# NetCamera.net
KiCad netlist of a schematic drawn in Altium Designer
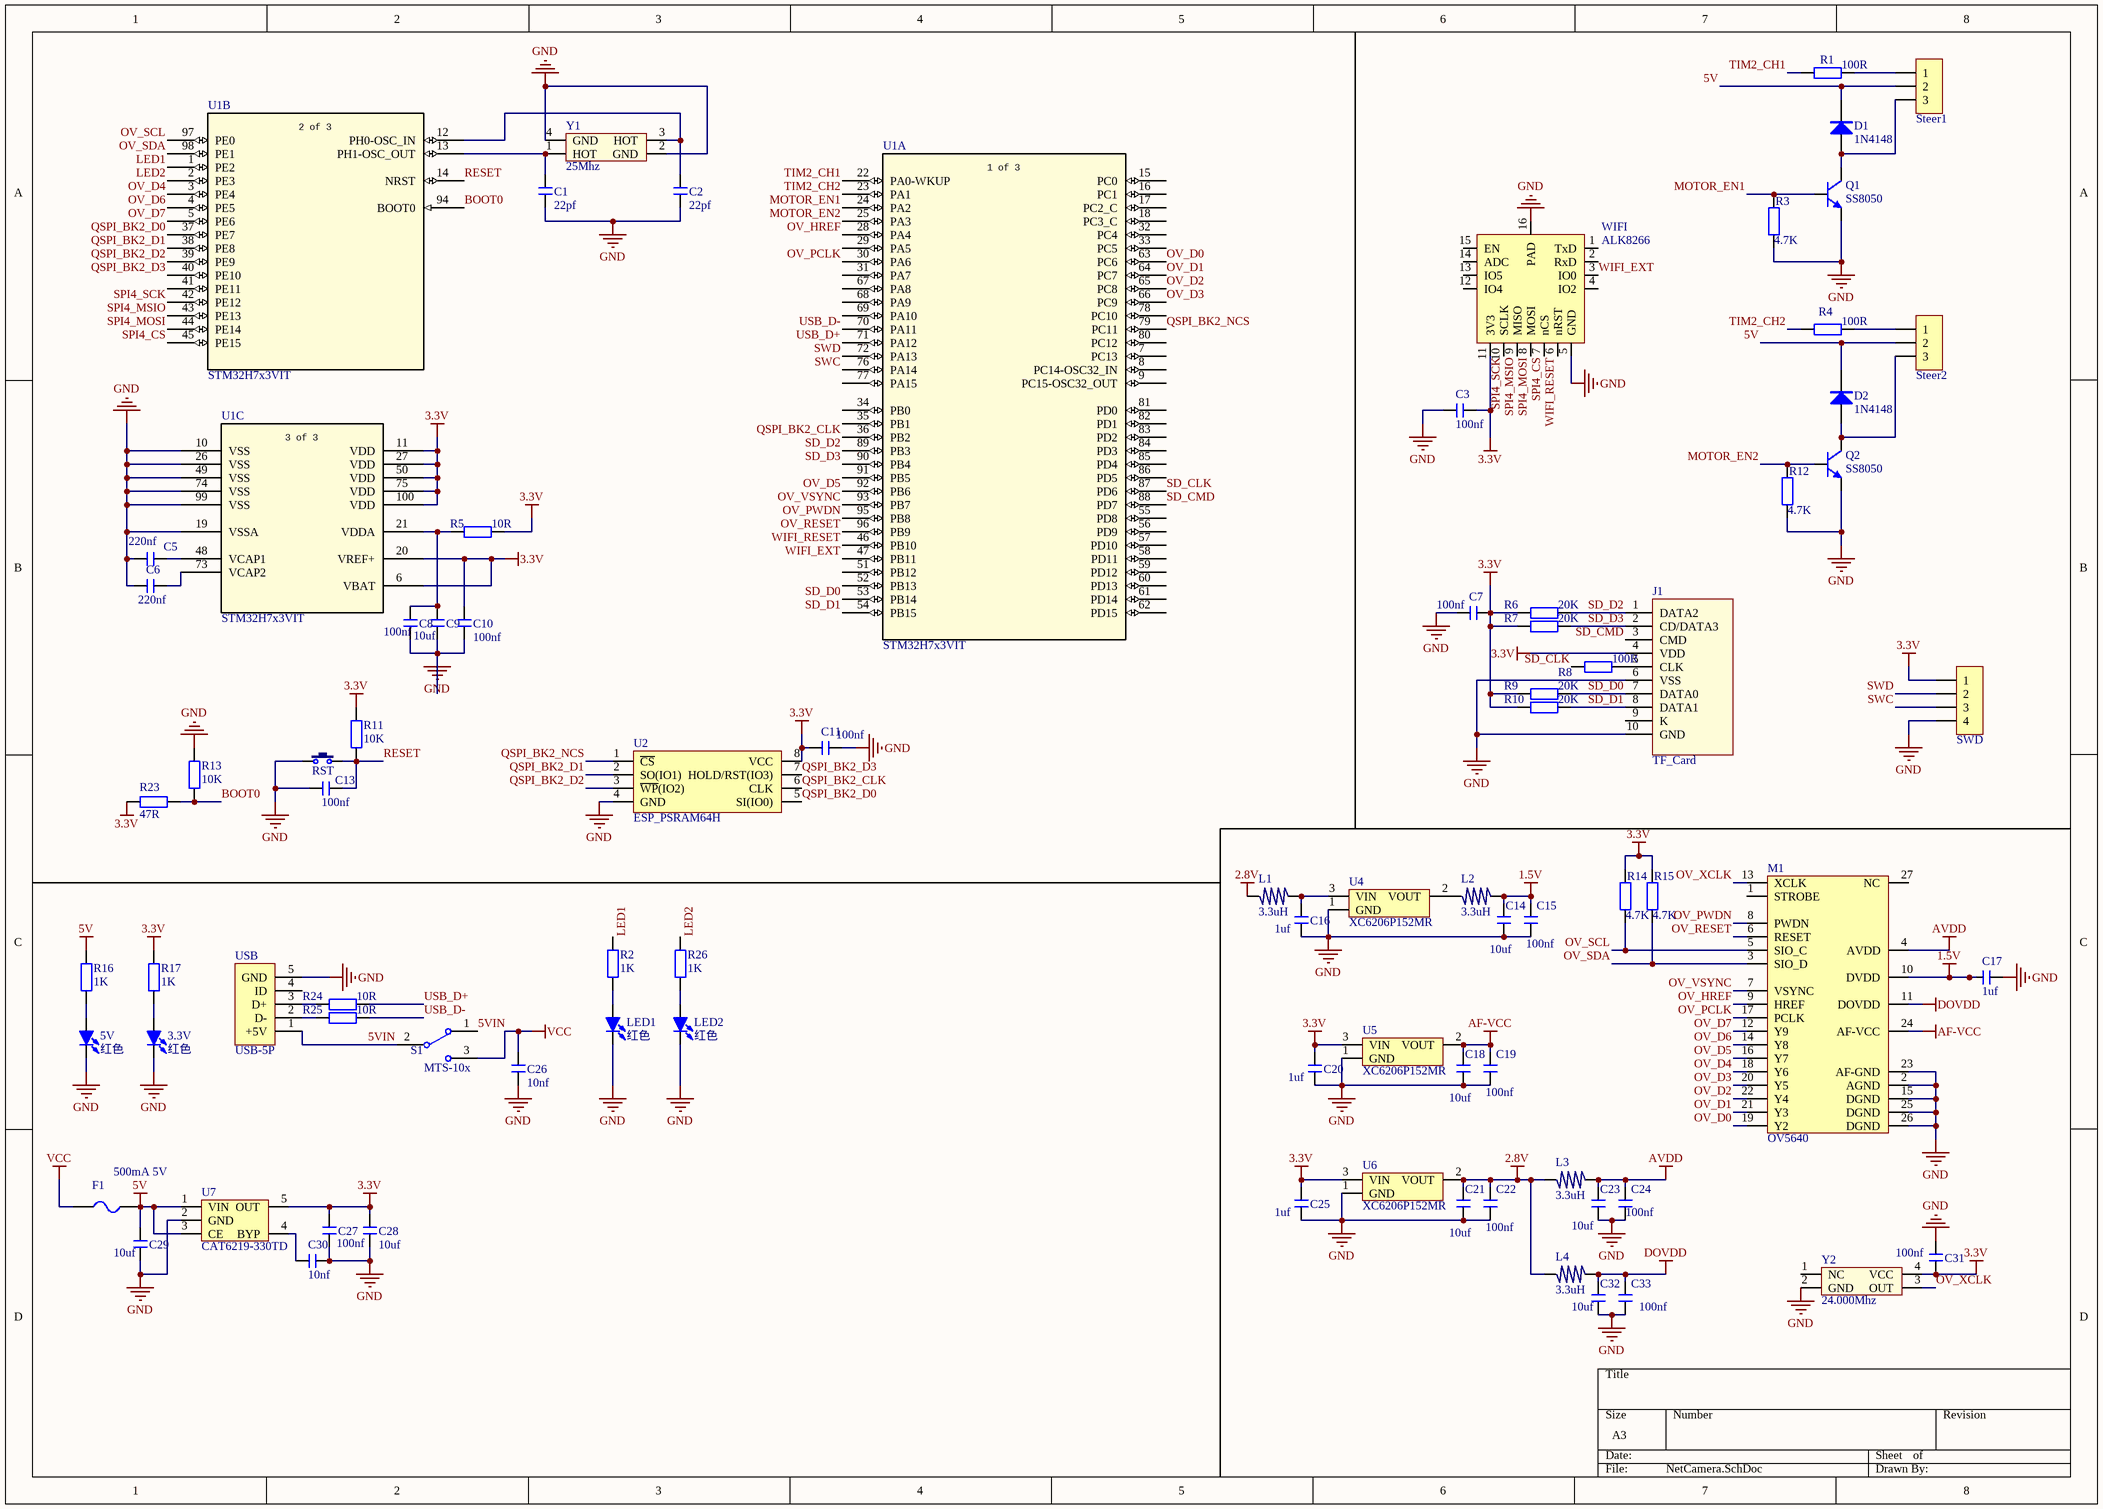
[diagram p0: NetCamera.SchDoc]

(export (version "E")
  (design (tool "Eeschema 10.0.6"))
  (components
    (comp (ref "3.3V")
      (value "红色")
      (footprint "LED 0603R")
      (description "贴片LED")
      (fields (field (name "版权归属") "源创客"))
      (libsource (lib "9.1   - LED") (part "LED-SMD"))
    )
    (comp (ref "5V")
      (value "红色")
      (footprint "LED 0603R")
      (description "贴片LED")
      (fields (field (name "版权归属") "源创客"))
      (libsource (lib "9.1   - LED") (part "LED-SMD"))
    )
    (comp (ref "C1")
      (value "22pf")
      (footprint "C 0603_L")
      (description "无极性贴片电容")
      (fields (field (name "版权归属") "源创客"))
      (libsource (lib "3.1   - 电阻-电容-电感") (part "C"))
    )
    (comp (ref "C2")
      (value "22pf")
      (footprint "C 0603_L")
      (description "无极性贴片电容")
      (fields (field (name "版权归属") "源创客"))
      (libsource (lib "3.1   - 电阻-电容-电感") (part "C"))
    )
    (comp (ref "C3")
      (value "100nf")
      (footprint "C 0603_L")
      (description "无极性贴片电容")
      (fields (field (name "版权归属") "源创客"))
      (libsource (lib "3.1   - 电阻-电容-电感") (part "C"))
    )
    (comp (ref "C5")
      (value "220nf")
      (footprint "C 0603_L")
      (description "无极性贴片电容")
      (fields (field (name "版权归属") "源创客"))
      (libsource (lib "3.1   - 电阻-电容-电感") (part "C"))
    )
    (comp (ref "C6")
      (value "220nf")
      (footprint "C 0603_L")
      (description "无极性贴片电容")
      (fields (field (name "版权归属") "源创客"))
      (libsource (lib "3.1   - 电阻-电容-电感") (part "C"))
    )
    (comp (ref "C7")
      (value "100nf")
      (footprint "C 0603_L")
      (description "无极性贴片电容")
      (fields (field (name "版权归属") "源创客"))
      (libsource (lib "3.1   - 电阻-电容-电感") (part "C"))
    )
    (comp (ref "C8")
      (value "100nf")
      (footprint "C 0603_L")
      (description "无极性贴片电容")
      (fields (field (name "版权归属") "源创客"))
      (libsource (lib "3.1   - 电阻-电容-电感") (part "C"))
    )
    (comp (ref "C9")
      (value "10uf")
      (footprint "C 0603_L")
      (description "无极性贴片电容")
      (fields (field (name "版权归属") "源创客"))
      (libsource (lib "3.1   - 电阻-电容-电感") (part "C"))
    )
    (comp (ref "C10")
      (value "100nf")
      (footprint "C 0603_L")
      (description "无极性贴片电容")
      (fields (field (name "版权归属") "源创客"))
      (libsource (lib "3.1   - 电阻-电容-电感") (part "C"))
    )
    (comp (ref "C11")
      (value "100nf")
      (footprint "C 0603_L")
      (description "无极性贴片电容")
      (fields (field (name "版权归属") "源创客"))
      (libsource (lib "3.1   - 电阻-电容-电感") (part "C"))
    )
    (comp (ref "C13")
      (value "100nf")
      (footprint "C 0603_L")
      (description "无极性贴片电容")
      (fields (field (name "版权归属") "源创客"))
      (libsource (lib "3.1   - 电阻-电容-电感") (part "C"))
    )
    (comp (ref "C14")
      (value "10uf")
      (footprint "C 0805_L")
      (description "无极性贴片电容")
      (fields (field (name "版权归属") "源创客"))
      (libsource (lib "3.1   - 电阻-电容-电感") (part "C"))
    )
    (comp (ref "C15")
      (value "100nf")
      (footprint "C 0603_L")
      (description "无极性贴片电容")
      (fields (field (name "版权归属") "源创客"))
      (libsource (lib "3.1   - 电阻-电容-电感") (part "C"))
    )
    (comp (ref "C16")
      (value "1uf")
      (footprint "C 0603_L")
      (description "无极性贴片电容")
      (fields (field (name "版权归属") "源创客"))
      (libsource (lib "3.1   - 电阻-电容-电感") (part "C"))
    )
    (comp (ref "C17")
      (value "1uf")
      (footprint "C 0805_L")
      (description "无极性贴片电容")
      (fields (field (name "版权归属") "源创客"))
      (libsource (lib "3.1   - 电阻-电容-电感") (part "C"))
    )
    (comp (ref "C18")
      (value "10uf")
      (footprint "C 0805_L")
      (description "无极性贴片电容")
      (fields (field (name "版权归属") "源创客"))
      (libsource (lib "3.1   - 电阻-电容-电感") (part "C"))
    )
    (comp (ref "C19")
      (value "100nf")
      (footprint "C 0603_L")
      (description "无极性贴片电容")
      (fields (field (name "版权归属") "源创客"))
      (libsource (lib "3.1   - 电阻-电容-电感") (part "C"))
    )
    (comp (ref "C20")
      (value "1uf")
      (footprint "C 0603_L")
      (description "无极性贴片电容")
      (fields (field (name "版权归属") "源创客"))
      (libsource (lib "3.1   - 电阻-电容-电感") (part "C"))
    )
    (comp (ref "C21")
      (value "10uf")
      (footprint "C 0805_L")
      (description "无极性贴片电容")
      (fields (field (name "版权归属") "源创客"))
      (libsource (lib "3.1   - 电阻-电容-电感") (part "C"))
    )
    (comp (ref "C22")
      (value "100nf")
      (footprint "C 0603_L")
      (description "无极性贴片电容")
      (fields (field (name "版权归属") "源创客"))
      (libsource (lib "3.1   - 电阻-电容-电感") (part "C"))
    )
    (comp (ref "C23")
      (value "10uf")
      (footprint "C 0805_L")
      (description "无极性贴片电容")
      (fields (field (name "版权归属") "源创客"))
      (libsource (lib "3.1   - 电阻-电容-电感") (part "C"))
    )
    (comp (ref "C24")
      (value "100nf")
      (footprint "C 0603_L")
      (description "无极性贴片电容")
      (fields (field (name "版权归属") "源创客"))
      (libsource (lib "3.1   - 电阻-电容-电感") (part "C"))
    )
    (comp (ref "C25")
      (value "1uf")
      (footprint "C 0603_L")
      (description "无极性贴片电容")
      (fields (field (name "版权归属") "源创客"))
      (libsource (lib "3.1   - 电阻-电容-电感") (part "C"))
    )
    (comp (ref "C26")
      (value "10nf")
      (footprint "C 0805_L")
      (description "无极性贴片电容")
      (fields (field (name "版权归属") "源创客"))
      (libsource (lib "3.1   - 电阻-电容-电感") (part "C"))
    )
    (comp (ref "C27")
      (value "100nf")
      (footprint "C 0603_L")
      (description "无极性贴片电容")
      (fields (field (name "版权归属") "源创客"))
      (libsource (lib "3.1   - 电阻-电容-电感") (part "C"))
    )
    (comp (ref "C28")
      (value "10uf")
      (footprint "C 0805_L")
      (description "无极性贴片电容")
      (fields (field (name "版权归属") "源创客"))
      (libsource (lib "3.1   - 电阻-电容-电感") (part "C"))
    )
    (comp (ref "C29")
      (value "10uf")
      (footprint "C 0603_L")
      (description "无极性贴片电容")
      (fields (field (name "版权归属") "源创客"))
      (libsource (lib "3.1   - 电阻-电容-电感") (part "C"))
    )
    (comp (ref "C30")
      (value "10nf")
      (footprint "C 0603_L")
      (description "无极性贴片电容")
      (fields (field (name "版权归属") "源创客"))
      (libsource (lib "3.1   - 电阻-电容-电感") (part "C"))
    )
    (comp (ref "C31")
      (value "100nf")
      (footprint "C 0603_L")
      (description "无极性贴片电容")
      (fields (field (name "版权归属") "源创客"))
      (libsource (lib "3.1   - 电阻-电容-电感") (part "C"))
    )
    (comp (ref "C32")
      (value "10uf")
      (footprint "C 0805_L")
      (description "无极性贴片电容")
      (fields (field (name "版权归属") "源创客"))
      (libsource (lib "3.1   - 电阻-电容-电感") (part "C"))
    )
    (comp (ref "C33")
      (value "100nf")
      (footprint "C 0603_L")
      (description "无极性贴片电容")
      (fields (field (name "版权归属") "源创客"))
      (libsource (lib "3.1   - 电阻-电容-电感") (part "C"))
    )
    (comp (ref "D1")
      (value "1N4148")
      (footprint "SOD-323")
      (description "高速开关二极管")
      (fields (field (name "版权归属") "源创客"))
      (libsource (lib "8.1   - 二极管-整流桥") (part "1N4148"))
    )
    (comp (ref "D2")
      (value "1N4148")
      (footprint "SOD-323")
      (description "高速开关二极管")
      (fields (field (name "版权归属") "源创客"))
      (libsource (lib "8.1   - 二极管-整流桥") (part "1N4148"))
    )
    (comp (ref "F1")
      (value "500mA 5V")
      (footprint "FU 0805")
      (description "贴片保险丝")
      (fields (field (name "版权归属") "源创客"))
      (libsource (lib "10.1 - 保险丝-晶振") (part "FU"))
    )
    (comp (ref "J1")
      (value "TF_Card")
      (footprint "Micro SD")
      (description "TF卡座")
      (fields (field (name "版权归属") "源创客"))
      (libsource (lib "4.1   - 接口类") (part "TF_Card"))
    )
    (comp (ref "L1") (value "3.3uH") (footprint "L 0805") (libsource (lib "ATK-OV5640摄像头模块封装库") (part "L")))
    (comp (ref "L2") (value "3.3uH") (footprint "L 0805") (libsource (lib "ATK-OV5640摄像头模块封装库") (part "L")))
    (comp (ref "L3") (value "3.3uH") (footprint "L 0805") (libsource (lib "ATK-OV5640摄像头模块封装库") (part "L")))
    (comp (ref "L4") (value "3.3uH") (footprint "L 0805") (libsource (lib "ATK-OV5640摄像头模块封装库") (part "L")))
    (comp (ref "LED1")
      (value "红色")
      (footprint "LED 0603R")
      (description "贴片LED")
      (fields (field (name "版权归属") "源创客"))
      (libsource (lib "9.1   - LED") (part "LED-SMD"))
    )
    (comp (ref "LED2")
      (value "红色")
      (footprint "LED 0603R")
      (description "贴片LED")
      (fields (field (name "版权归属") "源创客"))
      (libsource (lib "9.1   - LED") (part "LED-SMD"))
    )
    (comp (ref "M1")
      (value "OV5640")
      (footprint "OV5640-24")
      (description "OV5640模组,AF,FPC")
      (libsource (lib "ATK-OV5640摄像头模块封装库") (part "OV5640"))
    )
    (comp (ref "Q1")
      (value "SS8050")
      (footprint "SOT23-3N")
      (description "高频放大-NPN型")
      (fields (field (name "版权归属") "源创客"))
      (libsource (lib "6.2   - 三极管") (part "8050-SMD"))
    )
    (comp (ref "Q2")
      (value "SS8050")
      (footprint "SOT23-3N")
      (description "高频放大-NPN型")
      (fields (field (name "版权归属") "源创客"))
      (libsource (lib "6.2   - 三极管") (part "8050-SMD"))
    )
    (comp (ref "R1")
      (value "100R")
      (footprint "R 0603_L")
      (description "贴片电阻")
      (fields (field (name "版权归属") "源创客"))
      (libsource (lib "3.1   - 电阻-电容-电感") (part "R"))
    )
    (comp (ref "R2")
      (value "1K")
      (footprint "R 0603_L")
      (description "贴片电阻")
      (fields (field (name "版权归属") "源创客"))
      (libsource (lib "3.1   - 电阻-电容-电感") (part "R"))
    )
    (comp (ref "R3")
      (value "4.7K")
      (footprint "R 0603_L")
      (description "贴片电阻")
      (fields (field (name "版权归属") "源创客"))
      (libsource (lib "3.1   - 电阻-电容-电感") (part "R"))
    )
    (comp (ref "R4")
      (value "100R")
      (footprint "R 0603_L")
      (description "贴片电阻")
      (fields (field (name "版权归属") "源创客"))
      (libsource (lib "3.1   - 电阻-电容-电感") (part "R"))
    )
    (comp (ref "R5")
      (value "10R")
      (footprint "R 0603_L")
      (description "贴片电阻")
      (fields (field (name "版权归属") "源创客"))
      (libsource (lib "3.1   - 电阻-电容-电感") (part "R"))
    )
    (comp (ref "R6")
      (value "20K")
      (footprint "R 0603_L")
      (description "贴片电阻")
      (fields (field (name "版权归属") "源创客"))
      (libsource (lib "3.1   - 电阻-电容-电感") (part "R"))
    )
    (comp (ref "R7")
      (value "20K")
      (footprint "R 0603_L")
      (description "贴片电阻")
      (fields (field (name "版权归属") "源创客"))
      (libsource (lib "3.1   - 电阻-电容-电感") (part "R"))
    )
    (comp (ref "R8")
      (value "100R")
      (footprint "R 0603_L")
      (description "贴片电阻")
      (fields (field (name "版权归属") "源创客"))
      (libsource (lib "3.1   - 电阻-电容-电感") (part "R"))
    )
    (comp (ref "R9")
      (value "20K")
      (footprint "R 0603_L")
      (description "贴片电阻")
      (fields (field (name "版权归属") "源创客"))
      (libsource (lib "3.1   - 电阻-电容-电感") (part "R"))
    )
    (comp (ref "R10")
      (value "20K")
      (footprint "R 0603_L")
      (description "贴片电阻")
      (fields (field (name "版权归属") "源创客"))
      (libsource (lib "3.1   - 电阻-电容-电感") (part "R"))
    )
    (comp (ref "R11")
      (value "10K")
      (footprint "R 0603_L")
      (description "贴片电阻")
      (fields (field (name "版权归属") "源创客"))
      (libsource (lib "3.1   - 电阻-电容-电感") (part "R"))
    )
    (comp (ref "R12")
      (value "4.7K")
      (footprint "R 0603_L")
      (description "贴片电阻")
      (fields (field (name "版权归属") "源创客"))
      (libsource (lib "3.1   - 电阻-电容-电感") (part "R"))
    )
    (comp (ref "R13")
      (value "10K")
      (footprint "R 0603_L")
      (description "贴片电阻")
      (fields (field (name "版权归属") "源创客"))
      (libsource (lib "3.1   - 电阻-电容-电感") (part "R"))
    )
    (comp (ref "R14")
      (value "4.7K")
      (footprint "R 0603_L")
      (description "贴片电阻")
      (fields (field (name "版权归属") "源创客"))
      (libsource (lib "3.1   - 电阻-电容-电感") (part "R"))
    )
    (comp (ref "R15")
      (value "4.7K")
      (footprint "R 0603_L")
      (description "贴片电阻")
      (fields (field (name "版权归属") "源创客"))
      (libsource (lib "3.1   - 电阻-电容-电感") (part "R"))
    )
    (comp (ref "R16")
      (value "1K")
      (footprint "R 0603_L")
      (description "贴片电阻")
      (fields (field (name "版权归属") "源创客"))
      (libsource (lib "3.1   - 电阻-电容-电感") (part "R"))
    )
    (comp (ref "R17")
      (value "1K")
      (footprint "R 0603_L")
      (description "贴片电阻")
      (fields (field (name "版权归属") "源创客"))
      (libsource (lib "3.1   - 电阻-电容-电感") (part "R"))
    )
    (comp (ref "R23")
      (value "47R")
      (footprint "R 0603_L")
      (description "贴片电阻")
      (fields (field (name "版权归属") "源创客"))
      (libsource (lib "3.1   - 电阻-电容-电感") (part "R"))
    )
    (comp (ref "R24")
      (value "10R")
      (footprint "R 0603_L")
      (description "贴片电阻")
      (fields (field (name "版权归属") "源创客"))
      (libsource (lib "3.1   - 电阻-电容-电感") (part "R"))
    )
    (comp (ref "R25")
      (value "10R")
      (footprint "R 0603_L")
      (description "贴片电阻")
      (fields (field (name "版权归属") "源创客"))
      (libsource (lib "3.1   - 电阻-电容-电感") (part "R"))
    )
    (comp (ref "R26")
      (value "1K")
      (footprint "R 0603_L")
      (description "贴片电阻")
      (fields (field (name "版权归属") "源创客"))
      (libsource (lib "3.1   - 电阻-电容-电感") (part "R"))
    )
    (comp (ref "RST")
      (value "3x6x5")
      (footprint "TSW SMD-3*6*2.5")
      (description "3x6轻触开关")
      (fields (field (name "版权归属") "源创客"))
      (libsource (lib "5.1   - 按键-开关") (part "TSW 3x6"))
    )
    (comp (ref "S1")
      (value "MTS-10x")
      (footprint "8.5*3.5_弯3P")
      (description "MTS10x系列3脚扭子开关")
      (fields (field (name "版权归属") "源创客"))
      (libsource (lib "5.1   - 按键-开关") (part "MTS-10x"))
    )
    (comp (ref "Steer1")
      (value "HDR-1X3")
      (footprint "HDR2.54-LI-3P")
      (description "3P接插件")
      (fields (field (name "版权归属") "源创客"))
      (libsource (lib "4.5   - 接插件-脚距2.54") (part "Header 3"))
    )
    (comp (ref "Steer2")
      (value "HDR-1X3")
      (footprint "HDR2.54-LI-3P")
      (description "3P接插件")
      (fields (field (name "版权归属") "源创客"))
      (libsource (lib "4.5   - 接插件-脚距2.54") (part "Header 3"))
    )
    (comp (ref "SWD")
      (value "HDR-1X4")
      (footprint "HDR2.54-M-LI-4P")
      (description "4P接插件")
      (fields (field (name "版权归属") "源创客"))
      (libsource (lib "4.5   - 接插件-脚距2.54") (part "Header 4"))
    )
    (comp (ref "U1")
      (value "STM32H7x3VIT")
      (footprint "LQFP100_14x14mm")
      (description "Imported")
      (fields
        (field (name "MANUFACTURER_PART_NUMBER") "stm32h7x3vit")
        (field (name "COPYRIGHT") "Copyright (C) 2016 Accelerated Designs. All rights reserved")
      )
      (libsource (lib "STM32H50VBT6") (part "STM32H7x3VIT"))
    )
    (comp (ref "U2")
      (value "ESP_PSRAM64H")
      (footprint "SOP8_N")
      (description "W25Q128")
      (libsource (lib "STM32H743核心板封装库") (part "W25Q128"))
    )
    (comp (ref "U4")
      (value "XC6206P152MR")
      (footprint "SOT-23")
      (description "LDO,SOT23,1.2~5.0V")
      (libsource (lib "ATK-OV5640摄像头模块封装库") (part "XC6206"))
    )
    (comp (ref "U5")
      (value "XC6206P152MR")
      (footprint "SOT-23")
      (description "LDO,SOT23,1.2~5.0V")
      (libsource (lib "ATK-OV5640摄像头模块封装库") (part "XC6206"))
    )
    (comp (ref "U6")
      (value "XC6206P152MR")
      (footprint "SOT-23")
      (description "LDO,SOT23,1.2~5.0V")
      (libsource (lib "ATK-OV5640摄像头模块封装库") (part "XC6206"))
    )
    (comp (ref "U7")
      (value "CAT6219-330TD")
      (footprint "SOT-23-5")
      (description "3.3V 500mA LDO")
      (libsource (lib "STM32H743核心板封装库") (part "CAT6219-330TD"))
    )
    (comp (ref "USB")
      (value "USB-5P")
      (footprint "USB-MICRO_B")
      (description "微型USB母座")
      (fields (field (name "版权归属") "源创客"))
      (libsource (lib "4.1   - 接口类") (part "USB-5P"))
    )
    (comp (ref "WIFI") (value "ALK8266") (footprint "ALK8266") (libsource (lib "NetCamera") (part "ALK8266")))
    (comp (ref "Y1")
      (value "25Mhz")
      (footprint "XTAL3225")
      (description "3225贴片无源晶振")
      (libsource (lib "STM32H743核心板封装库") (part "XTAL_3225"))
    )
    (comp (ref "Y2")
      (value "24.000Mhz")
      (footprint "XTAL3225")
      (description "有源晶振")
      (libsource (lib "ATK-OV5640摄像头模块封装库") (part "XTAL_S"))
    )
  )
  (nets
    (net (code "1") (name "/5VIN") (class "Default")
      (node (ref "S1") (pin "1") (pinfunction "1_1") (pintype "passive"))
      (node (ref "S1") (pin "2") (pinfunction "2_2") (pintype "passive"))
      (node (ref "USB") (pin "1") (pinfunction "+5V_1") (pintype "passive"))
    )
    (net (code "2") (name "/BOOT0") (class "Default")
      (node (ref "R13") (pin "1") (pinfunction "1_1") (pintype "passive"))
      (node (ref "R23") (pin "1") (pinfunction "1_1") (pintype "passive"))
      (node (ref "U1") (pin "94") (pinfunction "BOOT0_94") (pintype "input"))
    )
    (net (code "3") (name "/LED1") (class "Default")
      (node (ref "R2") (pin "2") (pinfunction "2_2") (pintype "passive"))
      (node (ref "U1") (pin "1") (pinfunction "PE2_1") (pintype "bidirectional"))
    )
    (net (code "4") (name "/LED2") (class "Default")
      (node (ref "R26") (pin "2") (pinfunction "2_2") (pintype "passive"))
      (node (ref "U1") (pin "2") (pinfunction "PE3_2") (pintype "bidirectional"))
    )
    (net (code "5") (name "/MOTOR_EN1") (class "Default")
      (node (ref "Q1") (pin "1") (pinfunction "B_1") (pintype "passive"))
      (node (ref "R3") (pin "2") (pinfunction "2_2") (pintype "passive"))
      (node (ref "U1") (pin "24") (pinfunction "PA2_24") (pintype "bidirectional"))
    )
    (net (code "6") (name "/MOTOR_EN2") (class "Default")
      (node (ref "Q2") (pin "1") (pinfunction "B_1") (pintype "passive"))
      (node (ref "R12") (pin "2") (pinfunction "2_2") (pintype "passive"))
      (node (ref "U1") (pin "25") (pinfunction "PA3_25") (pintype "bidirectional"))
    )
    (net (code "7") (name "/OV_D0") (class "Default")
      (node (ref "M1") (pin "19") (pinfunction "Y2_19") (pintype "passive"))
      (node (ref "U1") (pin "63") (pinfunction "PC6_63") (pintype "bidirectional"))
    )
    (net (code "8") (name "/OV_D1") (class "Default")
      (node (ref "M1") (pin "21") (pinfunction "Y3_21") (pintype "passive"))
      (node (ref "U1") (pin "64") (pinfunction "PC7_64") (pintype "bidirectional"))
    )
    (net (code "9") (name "/OV_D2") (class "Default")
      (node (ref "M1") (pin "22") (pinfunction "Y4_22") (pintype "passive"))
      (node (ref "U1") (pin "65") (pinfunction "PC8_65") (pintype "bidirectional"))
    )
    (net (code "10") (name "/OV_D3") (class "Default")
      (node (ref "M1") (pin "20") (pinfunction "Y5_20") (pintype "passive"))
      (node (ref "U1") (pin "66") (pinfunction "PC9_66") (pintype "bidirectional"))
    )
    (net (code "11") (name "/OV_D4") (class "Default")
      (node (ref "M1") (pin "18") (pinfunction "Y6_18") (pintype "passive"))
      (node (ref "U1") (pin "3") (pinfunction "PE4_3") (pintype "bidirectional"))
    )
    (net (code "12") (name "/OV_D5") (class "Default")
      (node (ref "M1") (pin "16") (pinfunction "Y7_16") (pintype "passive"))
      (node (ref "U1") (pin "92") (pinfunction "PB6_92") (pintype "bidirectional"))
    )
    (net (code "13") (name "/OV_D6") (class "Default")
      (node (ref "M1") (pin "14") (pinfunction "Y8_14") (pintype "passive"))
      (node (ref "U1") (pin "4") (pinfunction "PE5_4") (pintype "bidirectional"))
    )
    (net (code "14") (name "/OV_D7") (class "Default")
      (node (ref "M1") (pin "12") (pinfunction "Y9_12") (pintype "passive"))
      (node (ref "U1") (pin "5") (pinfunction "PE6_5") (pintype "bidirectional"))
    )
    (net (code "15") (name "/OV_HREF") (class "Default")
      (node (ref "M1") (pin "9") (pinfunction "HREF_9") (pintype "passive"))
      (node (ref "U1") (pin "28") (pinfunction "PA4_28") (pintype "bidirectional"))
    )
    (net (code "16") (name "/OV_PCLK") (class "Default")
      (node (ref "M1") (pin "17") (pinfunction "PCLK_17") (pintype "passive"))
      (node (ref "U1") (pin "30") (pinfunction "PA6_30") (pintype "bidirectional"))
    )
    (net (code "17") (name "/OV_PWDN") (class "Default")
      (node (ref "M1") (pin "8") (pinfunction "PWDN_8") (pintype "passive"))
      (node (ref "U1") (pin "95") (pinfunction "PB8_95") (pintype "bidirectional"))
    )
    (net (code "18") (name "/OV_RESET") (class "Default")
      (node (ref "M1") (pin "6") (pinfunction "RESET_6") (pintype "passive"))
      (node (ref "U1") (pin "96") (pinfunction "PB9_96") (pintype "bidirectional"))
    )
    (net (code "19") (name "/OV_SCL") (class "Default")
      (node (ref "M1") (pin "5") (pinfunction "SIO_C_5") (pintype "passive"))
      (node (ref "R14") (pin "1") (pinfunction "1_1") (pintype "passive"))
      (node (ref "U1") (pin "97") (pinfunction "PE0_97") (pintype "bidirectional"))
    )
    (net (code "20") (name "/OV_SDA") (class "Default")
      (node (ref "M1") (pin "3") (pinfunction "SIO_D_3") (pintype "passive"))
      (node (ref "R15") (pin "1") (pinfunction "1_1") (pintype "passive"))
      (node (ref "U1") (pin "98") (pinfunction "PE1_98") (pintype "bidirectional"))
    )
    (net (code "21") (name "/OV_VSYNC") (class "Default")
      (node (ref "M1") (pin "7") (pinfunction "VSYNC_7") (pintype "passive"))
      (node (ref "U1") (pin "93") (pinfunction "PB7_93") (pintype "bidirectional"))
    )
    (net (code "22") (name "/OV_XCLK") (class "Default")
      (node (ref "M1") (pin "13") (pinfunction "XCLK_13") (pintype "passive"))
      (node (ref "Y2") (pin "3") (pinfunction "OUT_3") (pintype "passive"))
    )
    (net (code "23") (name "/QSPI_BK2_CLK") (class "Default")
      (node (ref "U1") (pin "36") (pinfunction "PB2_36") (pintype "bidirectional"))
      (node (ref "U2") (pin "6") (pinfunction "CLK_6") (pintype "passive"))
    )
    (net (code "24") (name "/QSPI_BK2_D0") (class "Default")
      (node (ref "U1") (pin "37") (pinfunction "PE7_37") (pintype "bidirectional"))
      (node (ref "U2") (pin "5") (pinfunction "SI(IO0)_5") (pintype "power_in"))
    )
    (net (code "25") (name "/QSPI_BK2_D1") (class "Default")
      (node (ref "U1") (pin "38") (pinfunction "PE8_38") (pintype "bidirectional"))
      (node (ref "U2") (pin "2") (pinfunction "SO(IO1)_2") (pintype "passive"))
    )
    (net (code "26") (name "/QSPI_BK2_D2") (class "Default")
      (node (ref "U1") (pin "39") (pinfunction "PE9_39") (pintype "bidirectional"))
      (node (ref "U2") (pin "3") (pinfunction "~{WP}(IO2)_3") (pintype "passive"))
    )
    (net (code "27") (name "/QSPI_BK2_D3") (class "Default")
      (node (ref "U1") (pin "40") (pinfunction "PE10_40") (pintype "bidirectional"))
      (node (ref "U2") (pin "7") (pinfunction "HOLD/RST(IO3)_7") (pintype "power_in"))
    )
    (net (code "28") (name "/QSPI_BK2_NCS") (class "Default")
      (node (ref "U1") (pin "79") (pinfunction "PC11_79") (pintype "bidirectional"))
      (node (ref "U2") (pin "1") (pinfunction "~{CS}_1") (pintype "passive"))
    )
    (net (code "29") (name "/RESET") (class "Default")
      (node (ref "C13") (pin "1") (pinfunction "1_1") (pintype "passive"))
      (node (ref "R11") (pin "1") (pinfunction "1_1") (pintype "passive"))
      (node (ref "RST") (pin "2") (pinfunction "2_2") (pintype "passive"))
      (node (ref "U1") (pin "14") (pinfunction "NRST_14") (pintype "bidirectional"))
    )
    (net (code "30") (name "/SD_CLK") (class "Default")
      (node (ref "R8") (pin "2") (pinfunction "2_2") (pintype "passive"))
      (node (ref "U1") (pin "87") (pinfunction "PD6_87") (pintype "bidirectional"))
    )
    (net (code "31") (name "/SD_CMD") (class "Default")
      (node (ref "J1") (pin "3") (pinfunction "CMD_3") (pintype "passive"))
      (node (ref "U1") (pin "88") (pinfunction "PD7_88") (pintype "bidirectional"))
    )
    (net (code "32") (name "/SD_D0") (class "Default")
      (node (ref "J1") (pin "7") (pinfunction "DATA0_7") (pintype "passive"))
      (node (ref "R9") (pin "1") (pinfunction "1_1") (pintype "passive"))
      (node (ref "U1") (pin "53") (pinfunction "PB14_53") (pintype "bidirectional"))
    )
    (net (code "33") (name "/SD_D1") (class "Default")
      (node (ref "J1") (pin "8") (pinfunction "DATA1_8") (pintype "passive"))
      (node (ref "R10") (pin "1") (pinfunction "1_1") (pintype "passive"))
      (node (ref "U1") (pin "54") (pinfunction "PB15_54") (pintype "bidirectional"))
    )
    (net (code "34") (name "/SD_D2") (class "Default")
      (node (ref "J1") (pin "1") (pinfunction "DATA2_1") (pintype "passive"))
      (node (ref "R6") (pin "1") (pinfunction "1_1") (pintype "passive"))
      (node (ref "U1") (pin "89") (pinfunction "PB3_89") (pintype "bidirectional"))
    )
    (net (code "35") (name "/SD_D3") (class "Default")
      (node (ref "J1") (pin "2") (pinfunction "CD/DATA3_2") (pintype "passive"))
      (node (ref "R7") (pin "1") (pinfunction "1_1") (pintype "passive"))
      (node (ref "U1") (pin "90") (pinfunction "PB4_90") (pintype "bidirectional"))
    )
    (net (code "36") (name "/SPI4_CS") (class "Default")
      (node (ref "U1") (pin "45") (pinfunction "PE15_45") (pintype "bidirectional"))
      (node (ref "WIFI") (pin "7") (pinfunction "nCS_7") (pintype "passive"))
    )
    (net (code "37") (name "/SPI4_MOSI") (class "Default")
      (node (ref "U1") (pin "44") (pinfunction "PE14_44") (pintype "bidirectional"))
      (node (ref "WIFI") (pin "8") (pinfunction "MOSI_8") (pintype "passive"))
    )
    (net (code "38") (name "/SPI4_MSIO") (class "Default")
      (node (ref "U1") (pin "43") (pinfunction "PE13_43") (pintype "bidirectional"))
      (node (ref "WIFI") (pin "9") (pinfunction "MISO_9") (pintype "passive"))
    )
    (net (code "39") (name "/SPI4_SCK") (class "Default")
      (node (ref "U1") (pin "42") (pinfunction "PE12_42") (pintype "bidirectional"))
      (node (ref "WIFI") (pin "10") (pinfunction "SCLK_10") (pintype "passive"))
    )
    (net (code "40") (name "/SWC") (class "Default")
      (node (ref "SWD") (pin "3") (pinfunction "3_3") (pintype "passive"))
      (node (ref "U1") (pin "76") (pinfunction "PA14_76") (pintype "bidirectional"))
    )
    (net (code "41") (name "/SWD") (class "Default")
      (node (ref "SWD") (pin "2") (pinfunction "2_2") (pintype "passive"))
      (node (ref "U1") (pin "72") (pinfunction "PA13_72") (pintype "bidirectional"))
    )
    (net (code "42") (name "/TIM2_CH1") (class "Default")
      (node (ref "R1") (pin "2") (pinfunction "2_2") (pintype "passive"))
      (node (ref "U1") (pin "22") (pinfunction "PA0-WKUP_22") (pintype "bidirectional"))
    )
    (net (code "43") (name "/TIM2_CH2") (class "Default")
      (node (ref "R4") (pin "2") (pinfunction "2_2") (pintype "passive"))
      (node (ref "U1") (pin "23") (pinfunction "PA1_23") (pintype "bidirectional"))
    )
    (net (code "44") (name "/USB_D+") (class "Default")
      (node (ref "R24") (pin "2") (pinfunction "2_2") (pintype "passive"))
      (node (ref "U1") (pin "71") (pinfunction "PA12_71") (pintype "bidirectional"))
    )
    (net (code "45") (name "/USB_D-") (class "Default")
      (node (ref "R25") (pin "2") (pinfunction "2_2") (pintype "passive"))
      (node (ref "U1") (pin "70") (pinfunction "PA11_70") (pintype "bidirectional"))
    )
    (net (code "46") (name "/WIFI_EXT") (class "Default")
      (node (ref "U1") (pin "47") (pinfunction "PB11_47") (pintype "bidirectional"))
      (node (ref "WIFI") (pin "3") (pinfunction "IO0_3") (pintype "passive"))
    )
    (net (code "47") (name "/WIFI_RESET") (class "Default")
      (node (ref "U1") (pin "46") (pinfunction "PB10_46") (pintype "bidirectional"))
      (node (ref "WIFI") (pin "6") (pinfunction "nRST_6") (pintype "passive"))
    )
    (net (code "48") (name "1.5V") (class "Default")
      (node (ref "C14") (pin "2") (pinfunction "2_2") (pintype "passive"))
      (node (ref "C15") (pin "2") (pinfunction "2_2") (pintype "passive"))
      (node (ref "C17") (pin "2") (pinfunction "2_2") (pintype "passive"))
      (node (ref "L2") (pin "2") (pintype "passive"))
      (node (ref "M1") (pin "10") (pinfunction "DVDD_10") (pintype "passive"))
    )
    (net (code "49") (name "2.8V") (class "Default")
      (node (ref "C21") (pin "2") (pinfunction "2_2") (pintype "passive"))
      (node (ref "C22") (pin "2") (pinfunction "2_2") (pintype "passive"))
      (node (ref "L1") (pin "1") (pintype "passive"))
      (node (ref "L3") (pin "1") (pintype "passive"))
      (node (ref "L4") (pin "1") (pintype "passive"))
      (node (ref "U6") (pin "2") (pinfunction "VOUT_2") (pintype "passive"))
    )
    (net (code "50") (name "3.3V") (class "Default")
      (node (ref "C10") (pin "2") (pinfunction "2_2") (pintype "passive"))
      (node (ref "C11") (pin "2") (pinfunction "2_2") (pintype "passive"))
      (node (ref "C20") (pin "2") (pinfunction "2_2") (pintype "passive"))
      (node (ref "C25") (pin "2") (pinfunction "2_2") (pintype "passive"))
      (node (ref "C27") (pin "2") (pinfunction "2_2") (pintype "passive"))
      (node (ref "C28") (pin "2") (pinfunction "2_2") (pintype "passive"))
      (node (ref "C3") (pin "1") (pinfunction "1_1") (pintype "passive"))
      (node (ref "C31") (pin "1") (pinfunction "1_1") (pintype "passive"))
      (node (ref "C7") (pin "1") (pinfunction "1_1") (pintype "passive"))
      (node (ref "J1") (pin "4") (pinfunction "VDD_4") (pintype "passive"))
      (node (ref "R10") (pin "2") (pinfunction "2_2") (pintype "passive"))
      (node (ref "R11") (pin "2") (pinfunction "2_2") (pintype "passive"))
      (node (ref "R14") (pin "2") (pinfunction "2_2") (pintype "passive"))
      (node (ref "R15") (pin "2") (pinfunction "2_2") (pintype "passive"))
      (node (ref "R17") (pin "2") (pinfunction "2_2") (pintype "passive"))
      (node (ref "R23") (pin "2") (pinfunction "2_2") (pintype "passive"))
      (node (ref "R5") (pin "2") (pinfunction "2_2") (pintype "passive"))
      (node (ref "R6") (pin "2") (pinfunction "2_2") (pintype "passive"))
      (node (ref "R7") (pin "2") (pinfunction "2_2") (pintype "passive"))
      (node (ref "R9") (pin "2") (pinfunction "2_2") (pintype "passive"))
      (node (ref "SWD") (pin "1") (pinfunction "1_1") (pintype "passive"))
      (node (ref "U1") (pin "100") (pinfunction "VDD_100") (pintype "power_in"))
      (node (ref "U1") (pin "11") (pinfunction "VDD_11") (pintype "power_in"))
      (node (ref "U1") (pin "20") (pinfunction "VREF+_20") (pintype "power_in"))
      (node (ref "U1") (pin "27") (pinfunction "VDD_27") (pintype "power_in"))
      (node (ref "U1") (pin "50") (pinfunction "VDD_50") (pintype "power_in"))
      (node (ref "U1") (pin "6") (pinfunction "VBAT_6") (pintype "power_in"))
      (node (ref "U1") (pin "75") (pinfunction "VDD_75") (pintype "power_in"))
      (node (ref "U2") (pin "8") (pinfunction "VCC_8") (pintype "passive"))
      (node (ref "U5") (pin "3") (pinfunction "VIN_3") (pintype "passive"))
      (node (ref "U6") (pin "3") (pinfunction "VIN_3") (pintype "passive"))
      (node (ref "U7") (pin "5") (pinfunction "OUT_5") (pintype "passive"))
      (node (ref "WIFI") (pin "11") (pinfunction "3V3_11") (pintype "passive"))
      (node (ref "Y2") (pin "4") (pinfunction "VCC_4") (pintype "passive"))
    )
    (net (code "51") (name "5V") (class "Default")
      (node (ref "C29") (pin "2") (pinfunction "2_2") (pintype "passive"))
      (node (ref "D1") (pin "2") (pinfunction "K_2") (pintype "passive"))
      (node (ref "D2") (pin "2") (pinfunction "K_2") (pintype "passive"))
      (node (ref "F1") (pin "2") (pinfunction "2_2") (pintype "passive"))
      (node (ref "R16") (pin "2") (pinfunction "2_2") (pintype "passive"))
      (node (ref "Steer1") (pin "2") (pinfunction "2_2") (pintype "passive"))
      (node (ref "Steer2") (pin "2") (pinfunction "2_2") (pintype "passive"))
      (node (ref "U7") (pin "1") (pinfunction "VIN_1") (pintype "passive"))
      (node (ref "U7") (pin "3") (pinfunction "CE_3") (pintype "passive"))
    )
    (net (code "52") (name "AF-VCC") (class "Default")
      (node (ref "C18") (pin "2") (pinfunction "2_2") (pintype "passive"))
      (node (ref "C19") (pin "2") (pinfunction "2_2") (pintype "passive"))
      (node (ref "M1") (pin "24") (pinfunction "AF-VCC_24") (pintype "passive"))
      (node (ref "U5") (pin "2") (pinfunction "VOUT_2") (pintype "passive"))
    )
    (net (code "53") (name "AVDD") (class "Default")
      (node (ref "C23") (pin "2") (pinfunction "2_2") (pintype "passive"))
      (node (ref "C24") (pin "2") (pinfunction "2_2") (pintype "passive"))
      (node (ref "L3") (pin "2") (pintype "passive"))
      (node (ref "M1") (pin "4") (pinfunction "AVDD_4") (pintype "passive"))
    )
    (net (code "54") (name "DOVDD") (class "Default")
      (node (ref "C32") (pin "2") (pinfunction "2_2") (pintype "passive"))
      (node (ref "C33") (pin "2") (pinfunction "2_2") (pintype "passive"))
      (node (ref "L4") (pin "2") (pintype "passive"))
      (node (ref "M1") (pin "11") (pinfunction "DOVDD_11") (pintype "passive"))
    )
    (net (code "55") (name "GND") (class "Default")
      (node (ref "3.3V") (pin "2") (pinfunction "K_2") (pintype "passive"))
      (node (ref "5V") (pin "2") (pinfunction "K_2") (pintype "passive"))
      (node (ref "C1") (pin "1") (pinfunction "1_1") (pintype "passive"))
      (node (ref "C10") (pin "1") (pinfunction "1_1") (pintype "passive"))
      (node (ref "C11") (pin "1") (pinfunction "1_1") (pintype "passive"))
      (node (ref "C13") (pin "2") (pinfunction "2_2") (pintype "passive"))
      (node (ref "C14") (pin "1") (pinfunction "1_1") (pintype "passive"))
      (node (ref "C15") (pin "1") (pinfunction "1_1") (pintype "passive"))
      (node (ref "C16") (pin "1") (pinfunction "1_1") (pintype "passive"))
      (node (ref "C17") (pin "1") (pinfunction "1_1") (pintype "passive"))
      (node (ref "C18") (pin "1") (pinfunction "1_1") (pintype "passive"))
      (node (ref "C19") (pin "1") (pinfunction "1_1") (pintype "passive"))
      (node (ref "C2") (pin "1") (pinfunction "1_1") (pintype "passive"))
      (node (ref "C20") (pin "1") (pinfunction "1_1") (pintype "passive"))
      (node (ref "C21") (pin "1") (pinfunction "1_1") (pintype "passive"))
      (node (ref "C22") (pin "1") (pinfunction "1_1") (pintype "passive"))
      (node (ref "C23") (pin "1") (pinfunction "1_1") (pintype "passive"))
      (node (ref "C24") (pin "1") (pinfunction "1_1") (pintype "passive"))
      (node (ref "C25") (pin "1") (pinfunction "1_1") (pintype "passive"))
      (node (ref "C26") (pin "1") (pinfunction "1_1") (pintype "passive"))
      (node (ref "C27") (pin "1") (pinfunction "1_1") (pintype "passive"))
      (node (ref "C28") (pin "1") (pinfunction "1_1") (pintype "passive"))
      (node (ref "C29") (pin "1") (pinfunction "1_1") (pintype "passive"))
      (node (ref "C3") (pin "2") (pinfunction "2_2") (pintype "passive"))
      (node (ref "C30") (pin "1") (pinfunction "1_1") (pintype "passive"))
      (node (ref "C31") (pin "2") (pinfunction "2_2") (pintype "passive"))
      (node (ref "C32") (pin "1") (pinfunction "1_1") (pintype "passive"))
      (node (ref "C33") (pin "1") (pinfunction "1_1") (pintype "passive"))
      (node (ref "C5") (pin "2") (pinfunction "2_2") (pintype "passive"))
      (node (ref "C6") (pin "2") (pinfunction "2_2") (pintype "passive"))
      (node (ref "C7") (pin "2") (pinfunction "2_2") (pintype "passive"))
      (node (ref "C8") (pin "1") (pinfunction "1_1") (pintype "passive"))
      (node (ref "C9") (pin "1") (pinfunction "1_1") (pintype "passive"))
      (node (ref "J1") (pin "10") (pinfunction "GND_10") (pintype "passive"))
      (node (ref "J1") (pin "6") (pinfunction "VSS_6") (pintype "passive"))
      (node (ref "LED1") (pin "2") (pinfunction "K_2") (pintype "passive"))
      (node (ref "LED2") (pin "2") (pinfunction "K_2") (pintype "passive"))
      (node (ref "M1") (pin "15") (pinfunction "DGND_15") (pintype "passive"))
      (node (ref "M1") (pin "2") (pinfunction "AGND_2") (pintype "passive"))
      (node (ref "M1") (pin "23") (pinfunction "AF-GND_23") (pintype "passive"))
      (node (ref "M1") (pin "25") (pinfunction "DGND_25") (pintype "passive"))
      (node (ref "M1") (pin "26") (pinfunction "DGND_26") (pintype "passive"))
      (node (ref "Q1") (pin "2") (pinfunction "E_2") (pintype "passive"))
      (node (ref "Q2") (pin "2") (pinfunction "E_2") (pintype "passive"))
      (node (ref "R12") (pin "1") (pinfunction "1_1") (pintype "passive"))
      (node (ref "R13") (pin "2") (pinfunction "2_2") (pintype "passive"))
      (node (ref "R3") (pin "1") (pinfunction "1_1") (pintype "passive"))
      (node (ref "RST") (pin "1") (pinfunction "1_1") (pintype "passive"))
      (node (ref "SWD") (pin "4") (pinfunction "4_4") (pintype "passive"))
      (node (ref "U1") (pin "10") (pinfunction "VSS_10") (pintype "power_in"))
      (node (ref "U1") (pin "19") (pinfunction "VSSA_19") (pintype "power_in"))
      (node (ref "U1") (pin "26") (pinfunction "VSS_26") (pintype "power_in"))
      (node (ref "U1") (pin "49") (pinfunction "VSS_49") (pintype "power_in"))
      (node (ref "U1") (pin "74") (pinfunction "VSS_74") (pintype "power_in"))
      (node (ref "U1") (pin "99") (pinfunction "VSS_99") (pintype "power_in"))
      (node (ref "U2") (pin "4") (pinfunction "GND_4") (pintype "passive"))
      (node (ref "U4") (pin "1") (pinfunction "GND_1") (pintype "passive"))
      (node (ref "U5") (pin "1") (pinfunction "GND_1") (pintype "passive"))
      (node (ref "U6") (pin "1") (pinfunction "GND_1") (pintype "passive"))
      (node (ref "U7") (pin "2") (pinfunction "GND_2") (pintype "passive"))
      (node (ref "USB") (pin "5") (pinfunction "GND_5") (pintype "passive"))
      (node (ref "WIFI") (pin "16") (pinfunction "PAD_16") (pintype "passive"))
      (node (ref "WIFI") (pin "5") (pinfunction "GND_5") (pintype "passive"))
      (node (ref "Y1") (pin "2") (pinfunction "GND_2") (pintype "passive"))
      (node (ref "Y1") (pin "4") (pinfunction "GND_4") (pintype "passive"))
      (node (ref "Y2") (pin "2") (pinfunction "GND_2") (pintype "passive"))
    )
    (net (code "56") (name "Net-(3.3V-A)") (class "Default")
      (node (ref "3.3V") (pin "1") (pinfunction "A_1") (pintype "passive"))
      (node (ref "R17") (pin "1") (pinfunction "1_1") (pintype "passive"))
    )
    (net (code "57") (name "Net-(5V-A)") (class "Default")
      (node (ref "5V") (pin "1") (pinfunction "A_1") (pintype "passive"))
      (node (ref "R16") (pin "1") (pinfunction "1_1") (pintype "passive"))
    )
    (net (code "58") (name "Net-(D1-A)") (class "Default")
      (node (ref "D1") (pin "1") (pinfunction "A_1") (pintype "passive"))
      (node (ref "Q1") (pin "3") (pinfunction "C_3") (pintype "passive"))
      (node (ref "Steer1") (pin "3") (pinfunction "3_3") (pintype "passive"))
    )
    (net (code "59") (name "Net-(D2-A)") (class "Default")
      (node (ref "D2") (pin "1") (pinfunction "A_1") (pintype "passive"))
      (node (ref "Q2") (pin "3") (pinfunction "C_3") (pintype "passive"))
      (node (ref "Steer2") (pin "3") (pinfunction "3_3") (pintype "passive"))
    )
    (net (code "60") (name "Net-(J1-CLK)") (class "Default")
      (node (ref "J1") (pin "5") (pinfunction "CLK_5") (pintype "passive"))
      (node (ref "R8") (pin "1") (pinfunction "1_1") (pintype "passive"))
    )
    (net (code "61") (name "Net-(LED1-A)") (class "Default")
      (node (ref "LED1") (pin "1") (pinfunction "A_1") (pintype "passive"))
      (node (ref "R2") (pin "1") (pinfunction "1_1") (pintype "passive"))
    )
    (net (code "62") (name "Net-(LED2-A)") (class "Default")
      (node (ref "LED2") (pin "1") (pinfunction "A_1") (pintype "passive"))
      (node (ref "R26") (pin "1") (pinfunction "1_1") (pintype "passive"))
    )
    (net (code "63") (name "Net-(R1-Pad1)") (class "Default")
      (node (ref "R1") (pin "1") (pinfunction "1_1") (pintype "passive"))
      (node (ref "Steer1") (pin "1") (pinfunction "1_1") (pintype "passive"))
    )
    (net (code "64") (name "Net-(R4-Pad1)") (class "Default")
      (node (ref "R4") (pin "1") (pinfunction "1_1") (pintype "passive"))
      (node (ref "Steer2") (pin "1") (pinfunction "1_1") (pintype "passive"))
    )
    (net (code "65") (name "Net-(U1B-PH0-OSC_IN)") (class "Default")
      (node (ref "C2") (pin "2") (pinfunction "2_2") (pintype "passive"))
      (node (ref "U1") (pin "12") (pinfunction "PH0-OSC_IN_12") (pintype "bidirectional"))
      (node (ref "Y1") (pin "3") (pinfunction "HOT_3") (pintype "passive"))
    )
    (net (code "66") (name "Net-(U1B-PH1-OSC_OUT)") (class "Default")
      (node (ref "C1") (pin "2") (pinfunction "2_2") (pintype "passive"))
      (node (ref "U1") (pin "13") (pinfunction "PH1-OSC_OUT_13") (pintype "bidirectional"))
      (node (ref "Y1") (pin "1") (pinfunction "HOT_1") (pintype "passive"))
    )
    (net (code "67") (name "Net-(U1C-VCAP1)") (class "Default")
      (node (ref "C5") (pin "1") (pinfunction "1_1") (pintype "passive"))
      (node (ref "U1") (pin "48") (pinfunction "VCAP1_48") (pintype "power_in"))
    )
    (net (code "68") (name "Net-(U1C-VCAP2)") (class "Default")
      (node (ref "C6") (pin "1") (pinfunction "1_1") (pintype "passive"))
      (node (ref "U1") (pin "73") (pinfunction "VCAP2_73") (pintype "power_in"))
    )
    (net (code "69") (name "Net-(U1C-VDDA)") (class "Default")
      (node (ref "C8") (pin "2") (pinfunction "2_2") (pintype "passive"))
      (node (ref "C9") (pin "2") (pinfunction "2_2") (pintype "passive"))
      (node (ref "R5") (pin "1") (pinfunction "1_1") (pintype "passive"))
      (node (ref "U1") (pin "21") (pinfunction "VDDA_21") (pintype "power_in"))
    )
    (net (code "70") (name "Net-(U4-VIN)") (class "Default")
      (node (ref "C16") (pin "2") (pinfunction "2_2") (pintype "passive"))
      (node (ref "L1") (pin "2") (pintype "passive"))
      (node (ref "U4") (pin "3") (pinfunction "VIN_3") (pintype "passive"))
    )
    (net (code "71") (name "Net-(U4-VOUT)") (class "Default")
      (node (ref "L2") (pin "1") (pintype "passive"))
      (node (ref "U4") (pin "2") (pinfunction "VOUT_2") (pintype "passive"))
    )
    (net (code "72") (name "Net-(U7-BYP)") (class "Default")
      (node (ref "C30") (pin "2") (pinfunction "2_2") (pintype "passive"))
      (node (ref "U7") (pin "4") (pinfunction "BYP_4") (pintype "passive"))
    )
    (net (code "73") (name "Net-(USB-D+)") (class "Default")
      (node (ref "R24") (pin "1") (pinfunction "1_1") (pintype "passive"))
      (node (ref "USB") (pin "3") (pinfunction "D+_3") (pintype "passive"))
    )
    (net (code "74") (name "Net-(USB-D-)") (class "Default")
      (node (ref "R25") (pin "1") (pinfunction "1_1") (pintype "passive"))
      (node (ref "USB") (pin "2") (pinfunction "D-_2") (pintype "passive"))
    )
    (net (code "75") (name "VCC") (class "Default")
      (node (ref "C26") (pin "2") (pinfunction "2_2") (pintype "passive"))
      (node (ref "F1") (pin "1") (pinfunction "1_1") (pintype "passive"))
      (node (ref "S1") (pin "3") (pinfunction "3_3") (pintype "passive"))
    )
    (net (code "76") (name "unconnected-(J1-K-Pad9)") (class "Default")
      (node (ref "J1") (pin "9") (pinfunction "K_9") (pintype "passive"))
    )
    (net (code "77") (name "unconnected-(M1-NC-Pad27)") (class "Default")
      (node (ref "M1") (pin "27") (pinfunction "NC_27") (pintype "passive"))
    )
    (net (code "78") (name "unconnected-(M1-STROBE-Pad1)") (class "Default")
      (node (ref "M1") (pin "1") (pinfunction "STROBE_1") (pintype "passive"))
    )
    (net (code "79") (name "unconnected-(U1A-PA5-Pad29)") (class "Default")
      (node (ref "U1") (pin "29") (pinfunction "PA5_29") (pintype "bidirectional"))
    )
    (net (code "80") (name "unconnected-(U1A-PA7-Pad31)") (class "Default")
      (node (ref "U1") (pin "31") (pinfunction "PA7_31") (pintype "bidirectional"))
    )
    (net (code "81") (name "unconnected-(U1A-PA8-Pad67)") (class "Default")
      (node (ref "U1") (pin "67") (pinfunction "PA8_67") (pintype "bidirectional"))
    )
    (net (code "82") (name "unconnected-(U1A-PA9-Pad68)") (class "Default")
      (node (ref "U1") (pin "68") (pinfunction "PA9_68") (pintype "bidirectional"))
    )
    (net (code "83") (name "unconnected-(U1A-PA10-Pad69)") (class "Default")
      (node (ref "U1") (pin "69") (pinfunction "PA10_69") (pintype "bidirectional"))
    )
    (net (code "84") (name "unconnected-(U1A-PA15-Pad77)") (class "Default")
      (node (ref "U1") (pin "77") (pinfunction "PA15_77") (pintype "bidirectional"))
    )
    (net (code "85") (name "unconnected-(U1A-PB0-Pad34)") (class "Default")
      (node (ref "U1") (pin "34") (pinfunction "PB0_34") (pintype "bidirectional"))
    )
    (net (code "86") (name "unconnected-(U1A-PB1-Pad35)") (class "Default")
      (node (ref "U1") (pin "35") (pinfunction "PB1_35") (pintype "bidirectional"))
    )
    (net (code "87") (name "unconnected-(U1A-PB5-Pad91)") (class "Default")
      (node (ref "U1") (pin "91") (pinfunction "PB5_91") (pintype "bidirectional"))
    )
    (net (code "88") (name "unconnected-(U1A-PB12-Pad51)") (class "Default")
      (node (ref "U1") (pin "51") (pinfunction "PB12_51") (pintype "bidirectional"))
    )
    (net (code "89") (name "unconnected-(U1A-PB13-Pad52)") (class "Default")
      (node (ref "U1") (pin "52") (pinfunction "PB13_52") (pintype "bidirectional"))
    )
    (net (code "90") (name "unconnected-(U1A-PC0-Pad15)") (class "Default")
      (node (ref "U1") (pin "15") (pinfunction "PC0_15") (pintype "bidirectional"))
    )
    (net (code "91") (name "unconnected-(U1A-PC1-Pad16)") (class "Default")
      (node (ref "U1") (pin "16") (pinfunction "PC1_16") (pintype "bidirectional"))
    )
    (net (code "92") (name "unconnected-(U1A-PC2_C-Pad17)") (class "Default")
      (node (ref "U1") (pin "17") (pinfunction "PC2_C_17") (pintype "bidirectional"))
    )
    (net (code "93") (name "unconnected-(U1A-PC3_C-Pad18)") (class "Default")
      (node (ref "U1") (pin "18") (pinfunction "PC3_C_18") (pintype "bidirectional"))
    )
    (net (code "94") (name "unconnected-(U1A-PC4-Pad32)") (class "Default")
      (node (ref "U1") (pin "32") (pinfunction "PC4_32") (pintype "bidirectional"))
    )
    (net (code "95") (name "unconnected-(U1A-PC5-Pad33)") (class "Default")
      (node (ref "U1") (pin "33") (pinfunction "PC5_33") (pintype "bidirectional"))
    )
    (net (code "96") (name "unconnected-(U1A-PC10-Pad78)") (class "Default")
      (node (ref "U1") (pin "78") (pinfunction "PC10_78") (pintype "bidirectional"))
    )
    (net (code "97") (name "unconnected-(U1A-PC12-Pad80)") (class "Default")
      (node (ref "U1") (pin "80") (pinfunction "PC12_80") (pintype "bidirectional"))
    )
    (net (code "98") (name "unconnected-(U1A-PC13-Pad7)") (class "Default")
      (node (ref "U1") (pin "7") (pinfunction "PC13_7") (pintype "bidirectional"))
    )
    (net (code "99") (name "unconnected-(U1A-PC14-OSC32_IN-Pad8)") (class "Default")
      (node (ref "U1") (pin "8") (pinfunction "PC14-OSC32_IN_8") (pintype "bidirectional"))
    )
    (net (code "100") (name "unconnected-(U1A-PC15-OSC32_OUT-Pad9)") (class "Default")
      (node (ref "U1") (pin "9") (pinfunction "PC15-OSC32_OUT_9") (pintype "bidirectional"))
    )
    (net (code "101") (name "unconnected-(U1A-PD0-Pad81)") (class "Default")
      (node (ref "U1") (pin "81") (pinfunction "PD0_81") (pintype "bidirectional"))
    )
    (net (code "102") (name "unconnected-(U1A-PD1-Pad82)") (class "Default")
      (node (ref "U1") (pin "82") (pinfunction "PD1_82") (pintype "bidirectional"))
    )
    (net (code "103") (name "unconnected-(U1A-PD2-Pad83)") (class "Default")
      (node (ref "U1") (pin "83") (pinfunction "PD2_83") (pintype "bidirectional"))
    )
    (net (code "104") (name "unconnected-(U1A-PD3-Pad84)") (class "Default")
      (node (ref "U1") (pin "84") (pinfunction "PD3_84") (pintype "bidirectional"))
    )
    (net (code "105") (name "unconnected-(U1A-PD4-Pad85)") (class "Default")
      (node (ref "U1") (pin "85") (pinfunction "PD4_85") (pintype "bidirectional"))
    )
    (net (code "106") (name "unconnected-(U1A-PD5-Pad86)") (class "Default")
      (node (ref "U1") (pin "86") (pinfunction "PD5_86") (pintype "bidirectional"))
    )
    (net (code "107") (name "unconnected-(U1A-PD8-Pad55)") (class "Default")
      (node (ref "U1") (pin "55") (pinfunction "PD8_55") (pintype "bidirectional"))
    )
    (net (code "108") (name "unconnected-(U1A-PD9-Pad56)") (class "Default")
      (node (ref "U1") (pin "56") (pinfunction "PD9_56") (pintype "bidirectional"))
    )
    (net (code "109") (name "unconnected-(U1A-PD10-Pad57)") (class "Default")
      (node (ref "U1") (pin "57") (pinfunction "PD10_57") (pintype "bidirectional"))
    )
    (net (code "110") (name "unconnected-(U1A-PD11-Pad58)") (class "Default")
      (node (ref "U1") (pin "58") (pinfunction "PD11_58") (pintype "bidirectional"))
    )
    (net (code "111") (name "unconnected-(U1A-PD12-Pad59)") (class "Default")
      (node (ref "U1") (pin "59") (pinfunction "PD12_59") (pintype "bidirectional"))
    )
    (net (code "112") (name "unconnected-(U1A-PD13-Pad60)") (class "Default")
      (node (ref "U1") (pin "60") (pinfunction "PD13_60") (pintype "bidirectional"))
    )
    (net (code "113") (name "unconnected-(U1A-PD14-Pad61)") (class "Default")
      (node (ref "U1") (pin "61") (pinfunction "PD14_61") (pintype "bidirectional"))
    )
    (net (code "114") (name "unconnected-(U1A-PD15-Pad62)") (class "Default")
      (node (ref "U1") (pin "62") (pinfunction "PD15_62") (pintype "bidirectional"))
    )
    (net (code "115") (name "unconnected-(U1B-PE11-Pad41)") (class "Default")
      (node (ref "U1") (pin "41") (pinfunction "PE11_41") (pintype "bidirectional"))
    )
    (net (code "116") (name "unconnected-(USB-ID-Pad4)") (class "Default")
      (node (ref "USB") (pin "4") (pinfunction "ID_4") (pintype "passive"))
    )
    (net (code "117") (name "unconnected-(WIFI-ADC-Pad14)") (class "Default")
      (node (ref "WIFI") (pin "14") (pinfunction "ADC_14") (pintype "passive"))
    )
    (net (code "118") (name "unconnected-(WIFI-EN-Pad15)") (class "Default")
      (node (ref "WIFI") (pin "15") (pinfunction "EN_15") (pintype "passive"))
    )
    (net (code "119") (name "unconnected-(WIFI-IO2-Pad4)") (class "Default")
      (node (ref "WIFI") (pin "4") (pinfunction "IO2_4") (pintype "passive"))
    )
    (net (code "120") (name "unconnected-(WIFI-IO4-Pad12)") (class "Default")
      (node (ref "WIFI") (pin "12") (pinfunction "IO4_12") (pintype "passive"))
    )
    (net (code "121") (name "unconnected-(WIFI-IO5-Pad13)") (class "Default")
      (node (ref "WIFI") (pin "13") (pinfunction "IO5_13") (pintype "passive"))
    )
    (net (code "122") (name "unconnected-(WIFI-RxD-Pad2)") (class "Default")
      (node (ref "WIFI") (pin "2") (pinfunction "RxD_2") (pintype "passive"))
    )
    (net (code "123") (name "unconnected-(WIFI-TxD-Pad1)") (class "Default")
      (node (ref "WIFI") (pin "1") (pinfunction "TxD_1") (pintype "passive"))
    )
    (net (code "124") (name "unconnected-(Y2-NC-Pad1)") (class "Default")
      (node (ref "Y2") (pin "1") (pinfunction "NC_1") (pintype "passive"))
    )
  )
)
